# score-board.net
KiCad netlist of a schematic drawn in EAGLE
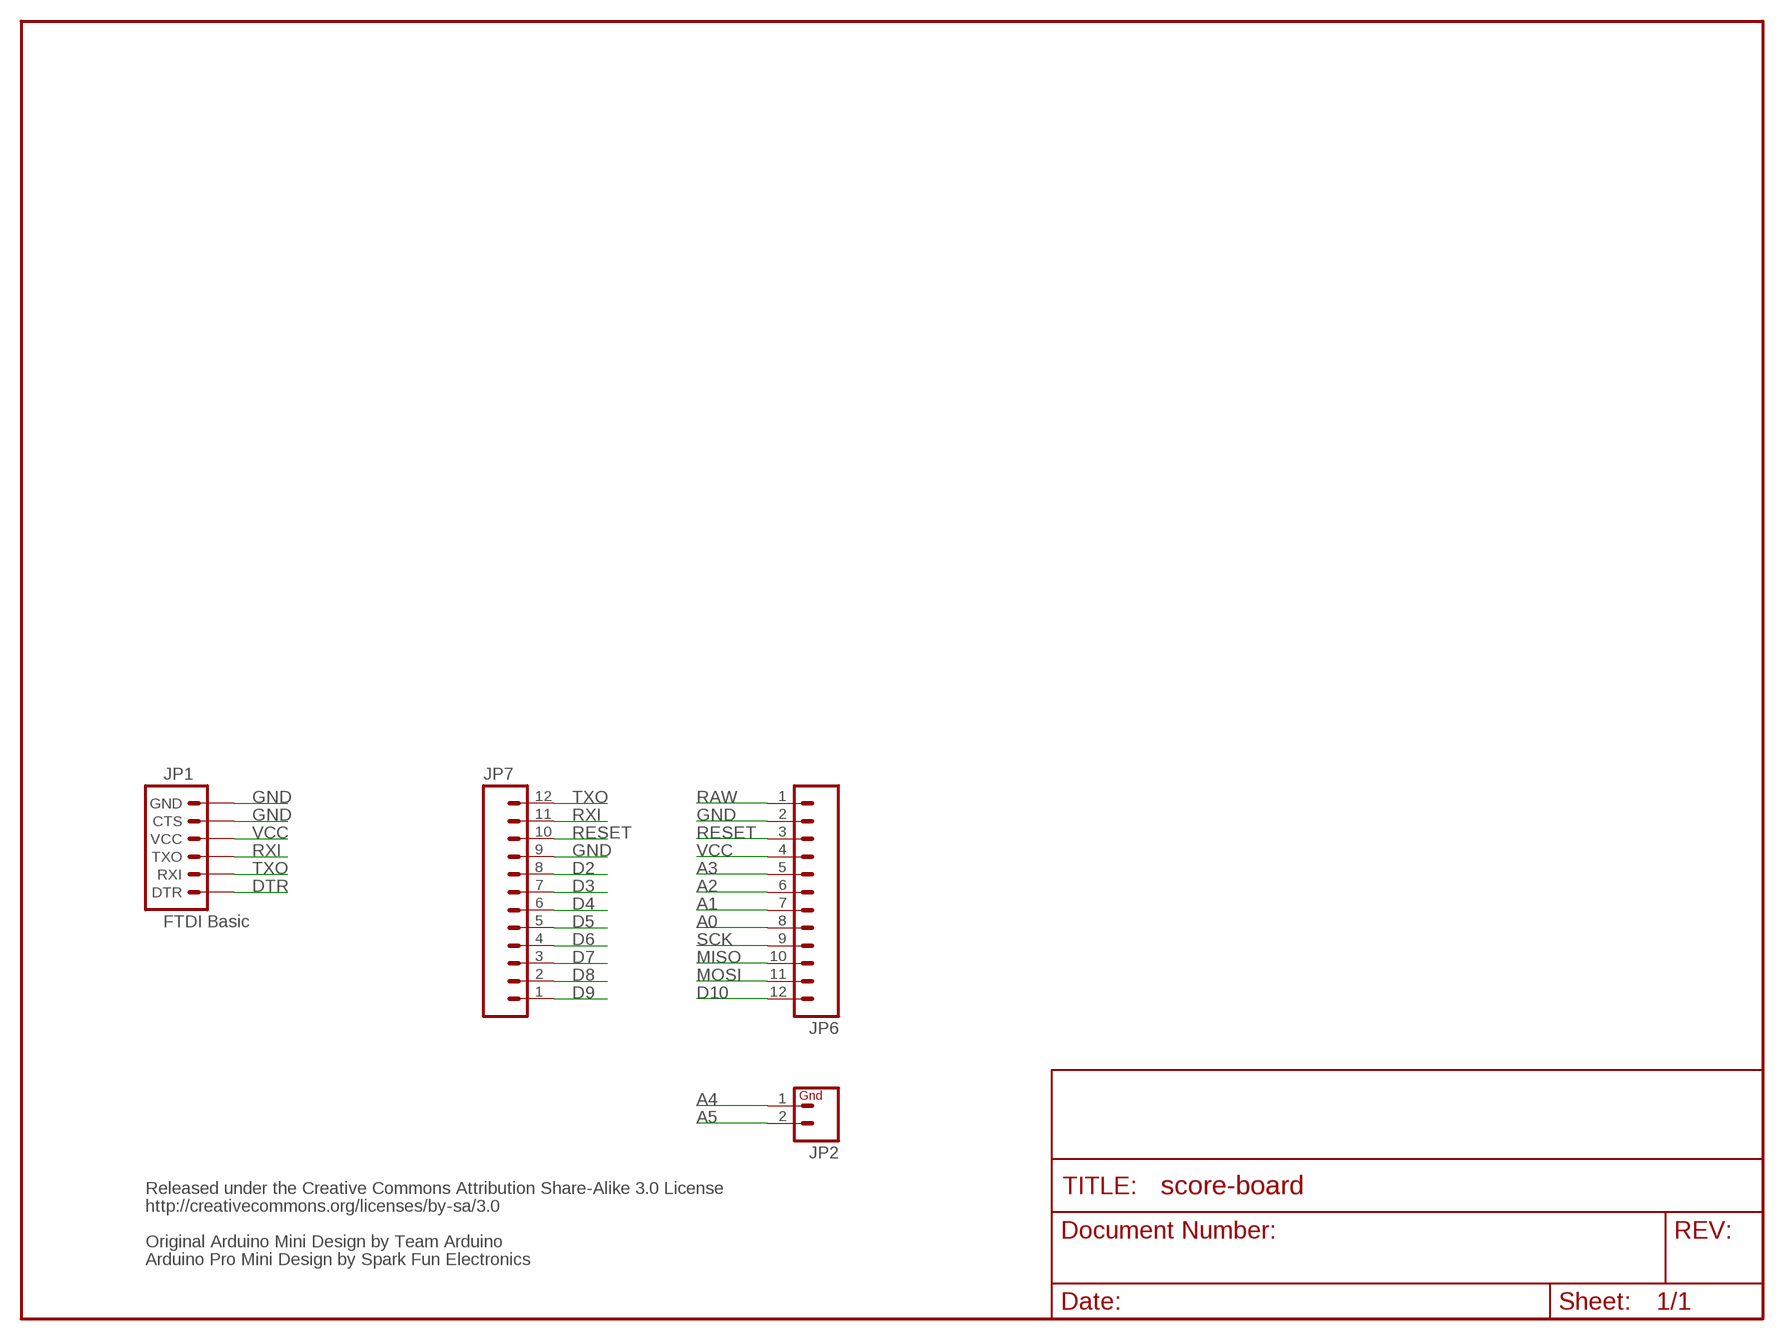
[diagram p0: schematic, sheet 1]

(export (version "E")
  (design (tool "Eeschema 10.0.6"))
  (components
    (comp (ref "JP1")
      (value "FTDI Basic")
      (footprint "eagle-import:1X06")
      (libsource (lib "eagle-import") (part "ARDUINO_SERIAL_PROGRAMPTH"))
    )
    (comp (ref "JP2")
      (value "M02PTH")
      (footprint "eagle-import:1X02")
      (libsource (lib "eagle-import") (part "M02PTH"))
    )
    (comp (ref "JP6")
      (value "M12PTH")
      (footprint "eagle-import:1X12")
      (libsource (lib "eagle-import") (part "M12PTH"))
    )
    (comp (ref "JP7")
      (value "M12PTH")
      (footprint "eagle-import:1X12")
      (libsource (lib "eagle-import") (part "M12PTH"))
    )
  )
  (nets
    (net (code "1") (name "/A0") (class "Default")
      (node (ref "JP6") (pin "8") (pinfunction "8_8") (pintype "passive"))
    )
    (net (code "2") (name "/A1") (class "Default")
      (node (ref "JP6") (pin "7") (pinfunction "7_7") (pintype "passive"))
    )
    (net (code "3") (name "/A2") (class "Default")
      (node (ref "JP6") (pin "6") (pinfunction "6_6") (pintype "passive"))
    )
    (net (code "4") (name "/A3") (class "Default")
      (node (ref "JP6") (pin "5") (pinfunction "5_5") (pintype "passive"))
    )
    (net (code "5") (name "/A4") (class "Default")
      (node (ref "JP2") (pin "1") (pinfunction "1_1") (pintype "passive"))
    )
    (net (code "6") (name "/A5") (class "Default")
      (node (ref "JP2") (pin "2") (pinfunction "2_2") (pintype "passive"))
    )
    (net (code "7") (name "/D2") (class "Default")
      (node (ref "JP7") (pin "8") (pinfunction "8_8") (pintype "passive"))
    )
    (net (code "8") (name "/D3") (class "Default")
      (node (ref "JP7") (pin "7") (pinfunction "7_7") (pintype "passive"))
    )
    (net (code "9") (name "/D4") (class "Default")
      (node (ref "JP7") (pin "6") (pinfunction "6_6") (pintype "passive"))
    )
    (net (code "10") (name "/D5") (class "Default")
      (node (ref "JP7") (pin "5") (pinfunction "5_5") (pintype "passive"))
    )
    (net (code "11") (name "/D6") (class "Default")
      (node (ref "JP7") (pin "4") (pinfunction "4_4") (pintype "passive"))
    )
    (net (code "12") (name "/D7") (class "Default")
      (node (ref "JP7") (pin "3") (pinfunction "3_3") (pintype "passive"))
    )
    (net (code "13") (name "/D8") (class "Default")
      (node (ref "JP7") (pin "2") (pinfunction "2_2") (pintype "passive"))
    )
    (net (code "14") (name "/D9") (class "Default")
      (node (ref "JP7") (pin "1") (pinfunction "1_1") (pintype "passive"))
    )
    (net (code "15") (name "/D10") (class "Default")
      (node (ref "JP6") (pin "12") (pinfunction "12_12") (pintype "passive"))
    )
    (net (code "16") (name "/DTR") (class "Default")
      (node (ref "JP1") (pin "1") (pinfunction "DTR_1") (pintype "passive"))
    )
    (net (code "17") (name "/GND") (class "Default")
      (node (ref "JP1") (pin "5") (pinfunction "CTS_5") (pintype "passive"))
      (node (ref "JP1") (pin "6") (pinfunction "GND_6") (pintype "passive"))
      (node (ref "JP6") (pin "2") (pinfunction "2_2") (pintype "passive"))
      (node (ref "JP7") (pin "9") (pinfunction "9_9") (pintype "passive"))
    )
    (net (code "18") (name "/MISO") (class "Default")
      (node (ref "JP6") (pin "10") (pinfunction "10_10") (pintype "passive"))
    )
    (net (code "19") (name "/MOSI") (class "Default")
      (node (ref "JP6") (pin "11") (pinfunction "11_11") (pintype "passive"))
    )
    (net (code "20") (name "/RAW") (class "Default")
      (node (ref "JP6") (pin "1") (pinfunction "1_1") (pintype "passive"))
    )
    (net (code "21") (name "/RESET") (class "Default")
      (node (ref "JP6") (pin "3") (pinfunction "3_3") (pintype "passive"))
      (node (ref "JP7") (pin "10") (pinfunction "10_10") (pintype "passive"))
    )
    (net (code "22") (name "/RXI") (class "Default")
      (node (ref "JP1") (pin "3") (pinfunction "TXO_3") (pintype "passive"))
      (node (ref "JP7") (pin "11") (pinfunction "11_11") (pintype "passive"))
    )
    (net (code "23") (name "/SCK") (class "Default")
      (node (ref "JP6") (pin "9") (pinfunction "9_9") (pintype "passive"))
    )
    (net (code "24") (name "/TXO") (class "Default")
      (node (ref "JP1") (pin "2") (pinfunction "RXI_2") (pintype "passive"))
      (node (ref "JP7") (pin "12") (pinfunction "12_12") (pintype "passive"))
    )
    (net (code "25") (name "/VCC") (class "Default")
      (node (ref "JP1") (pin "4") (pinfunction "VCC_4") (pintype "passive"))
      (node (ref "JP6") (pin "4") (pinfunction "4_4") (pintype "passive"))
    )
  )
)
